# Saturn_Cartage.net
KiCad netlist of a schematic drawn in Altium Designer
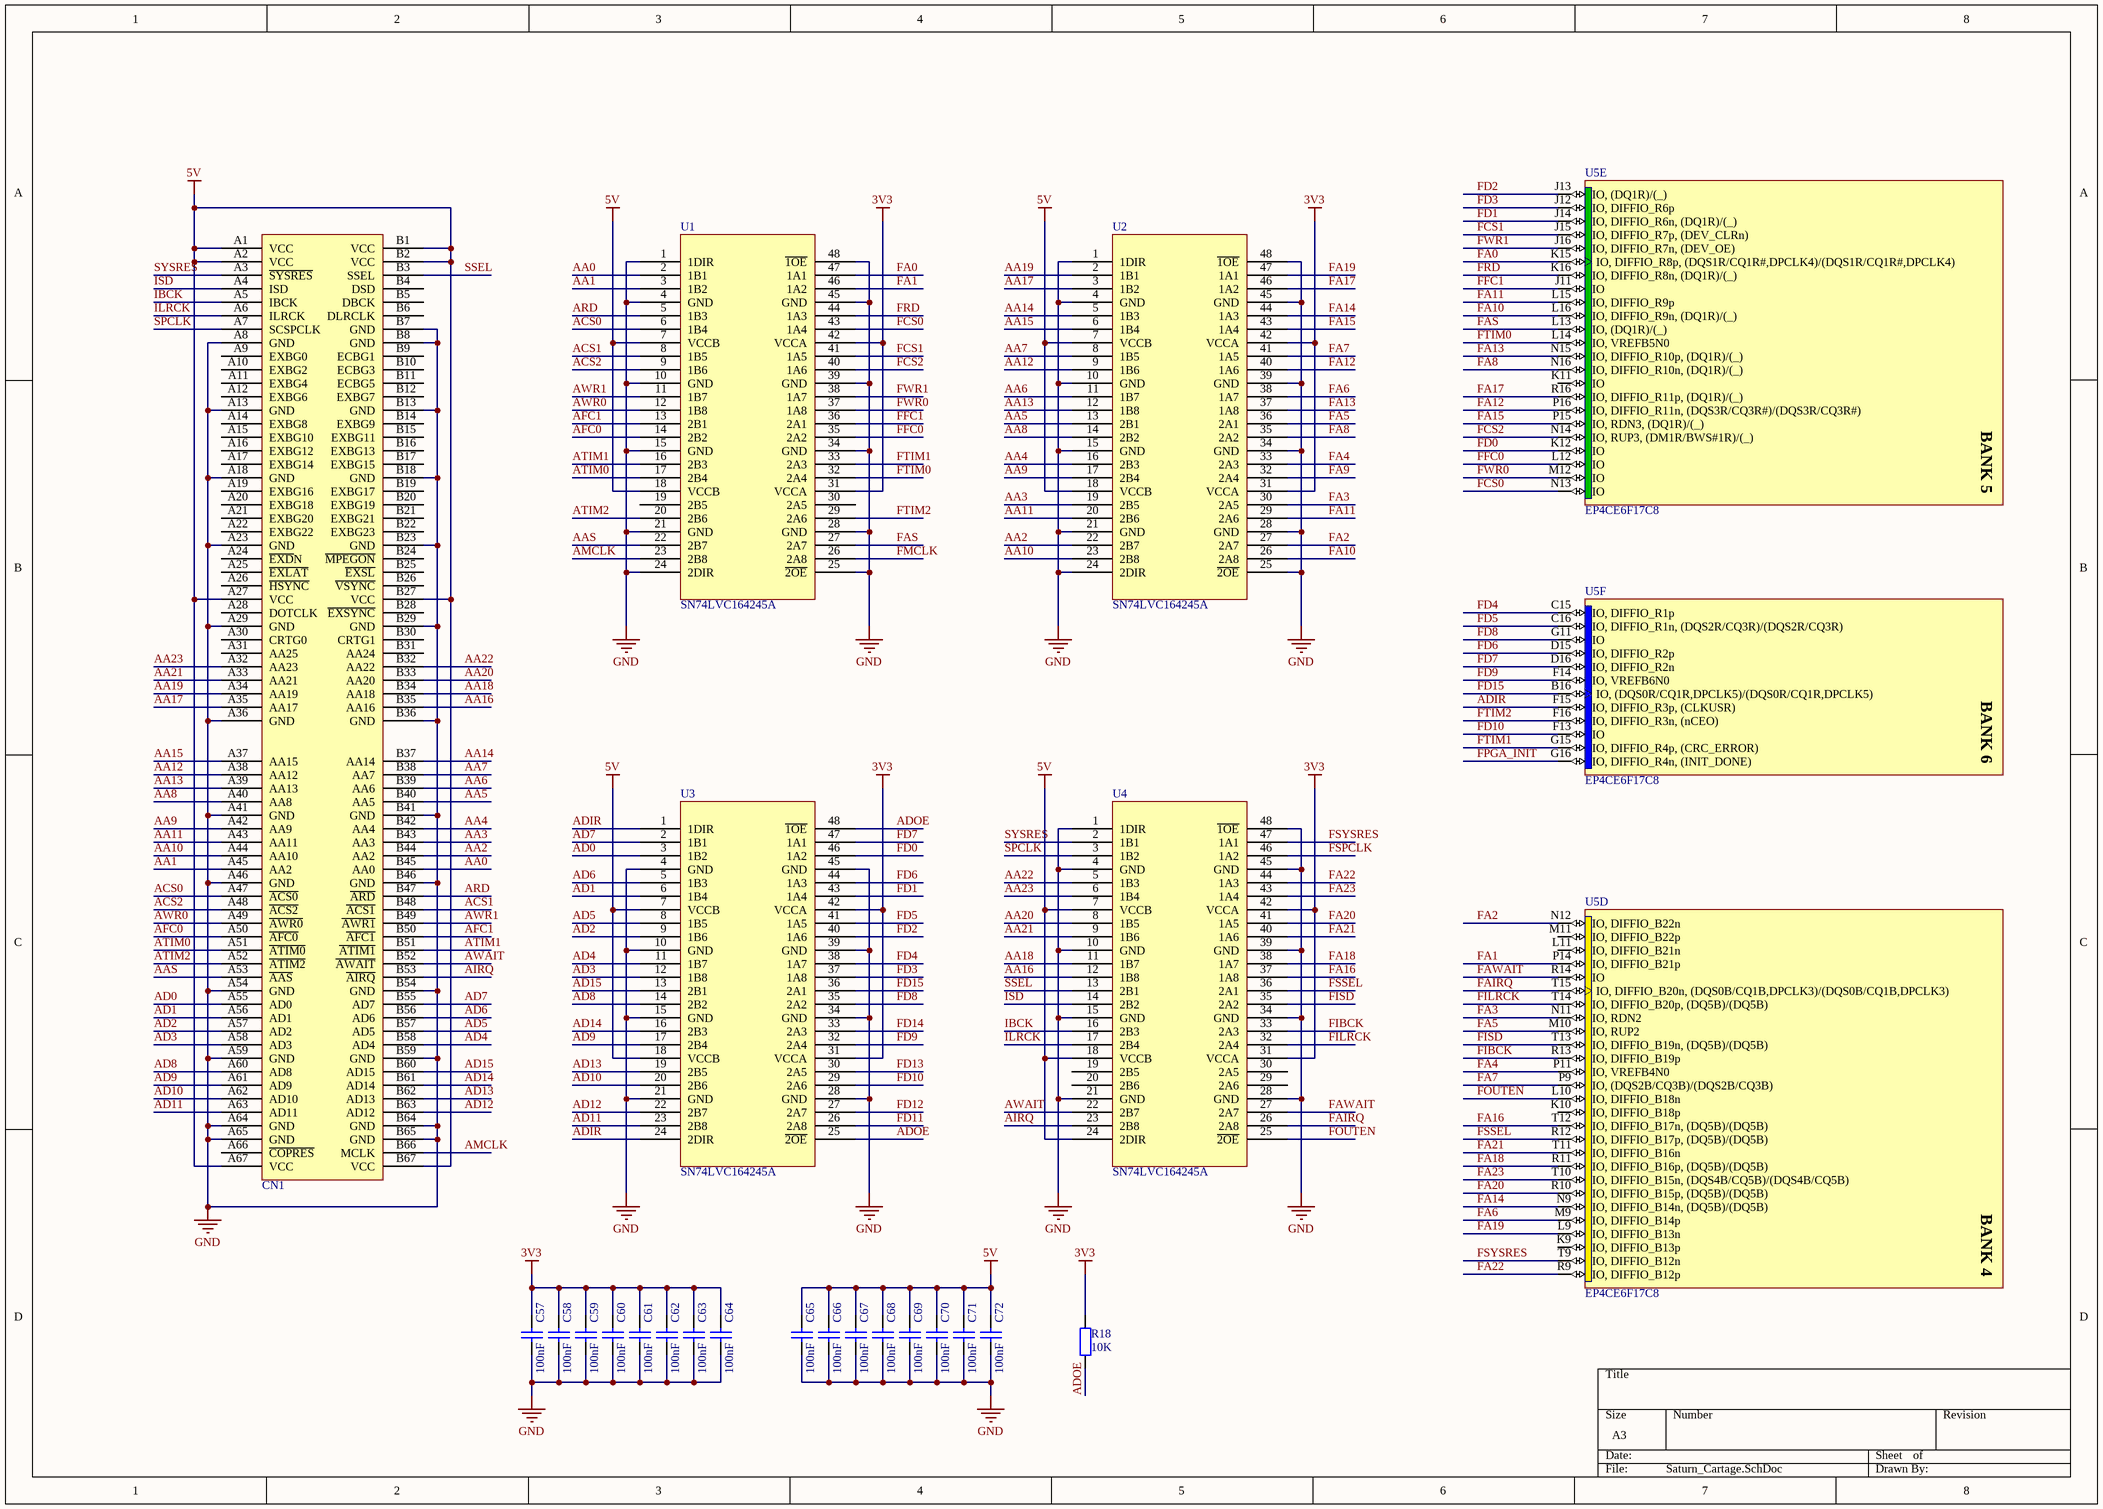
[diagram p0: Saturn_Cartage.SchDoc]

(export (version "E")
  (design (tool "Eeschema 10.0.6"))
  (components
    (comp (ref "C57")
      (value "100nF")
      (footprint "C0603")
      (description "Capacitor")
      (fields (field (name "PUBLISHER") "Altium Limited"))
      (libsource (lib "Miscellaneous Devices") (part "Cap"))
    )
    (comp (ref "C58")
      (value "100nF")
      (footprint "C0603")
      (description "Capacitor")
      (fields (field (name "PUBLISHER") "Altium Limited"))
      (libsource (lib "Miscellaneous Devices") (part "Cap"))
    )
    (comp (ref "C59")
      (value "100nF")
      (footprint "C0603")
      (description "Capacitor")
      (fields (field (name "PUBLISHER") "Altium Limited"))
      (libsource (lib "Miscellaneous Devices") (part "Cap"))
    )
    (comp (ref "C60")
      (value "100nF")
      (footprint "C0603")
      (description "Capacitor")
      (fields (field (name "PUBLISHER") "Altium Limited"))
      (libsource (lib "Miscellaneous Devices") (part "Cap"))
    )
    (comp (ref "C61")
      (value "100nF")
      (footprint "C0603")
      (description "Capacitor")
      (fields (field (name "PUBLISHER") "Altium Limited"))
      (libsource (lib "Miscellaneous Devices") (part "Cap"))
    )
    (comp (ref "C62")
      (value "100nF")
      (footprint "C0603")
      (description "Capacitor")
      (fields (field (name "PUBLISHER") "Altium Limited"))
      (libsource (lib "Miscellaneous Devices") (part "Cap"))
    )
    (comp (ref "C63")
      (value "100nF")
      (footprint "C0603")
      (description "Capacitor")
      (fields (field (name "PUBLISHER") "Altium Limited"))
      (libsource (lib "Miscellaneous Devices") (part "Cap"))
    )
    (comp (ref "C64")
      (value "100nF")
      (footprint "C0603")
      (description "Capacitor")
      (fields (field (name "PUBLISHER") "Altium Limited"))
      (libsource (lib "Miscellaneous Devices") (part "Cap"))
    )
    (comp (ref "C65")
      (value "100nF")
      (footprint "C0603")
      (description "Capacitor")
      (fields (field (name "PUBLISHER") "Altium Limited"))
      (libsource (lib "Miscellaneous Devices") (part "Cap"))
    )
    (comp (ref "C66")
      (value "100nF")
      (footprint "C0603")
      (description "Capacitor")
      (fields (field (name "PUBLISHER") "Altium Limited"))
      (libsource (lib "Miscellaneous Devices") (part "Cap"))
    )
    (comp (ref "C67")
      (value "100nF")
      (footprint "C0603")
      (description "Capacitor")
      (fields (field (name "PUBLISHER") "Altium Limited"))
      (libsource (lib "Miscellaneous Devices") (part "Cap"))
    )
    (comp (ref "C68")
      (value "100nF")
      (footprint "C0603")
      (description "Capacitor")
      (fields (field (name "PUBLISHER") "Altium Limited"))
      (libsource (lib "Miscellaneous Devices") (part "Cap"))
    )
    (comp (ref "C69")
      (value "100nF")
      (footprint "C0603")
      (description "Capacitor")
      (fields (field (name "PUBLISHER") "Altium Limited"))
      (libsource (lib "Miscellaneous Devices") (part "Cap"))
    )
    (comp (ref "C70")
      (value "100nF")
      (footprint "C0603")
      (description "Capacitor")
      (fields (field (name "PUBLISHER") "Altium Limited"))
      (libsource (lib "Miscellaneous Devices") (part "Cap"))
    )
    (comp (ref "C71")
      (value "100nF")
      (footprint "C0603")
      (description "Capacitor")
      (fields (field (name "PUBLISHER") "Altium Limited"))
      (libsource (lib "Miscellaneous Devices") (part "Cap"))
    )
    (comp (ref "C72")
      (value "100nF")
      (footprint "C0603")
      (description "Capacitor")
      (fields (field (name "PUBLISHER") "Altium Limited"))
      (libsource (lib "Miscellaneous Devices") (part "Cap"))
    )
    (comp (ref "CN1")
      (value "SaturnCartage")
      (footprint "Saturn_cart")
      (libsource (lib "ssmaster_1") (part "SaturnCartage"))
    )
    (comp (ref "R18")
      (value "10K")
      (footprint "R0603")
      (description "Resistor")
      (fields (field (name "PUBLISHER") "Altium Limited"))
      (libsource (lib "Miscellaneous Devices") (part "Res2"))
    )
    (comp (ref "U1")
      (value "SN74LVC164245A")
      (footprint "DGG048")
      (libsource (lib "ssmaster_1") (part "SN74LVC164245A"))
    )
    (comp (ref "U2")
      (value "SN74LVC164245A")
      (footprint "DGG048")
      (libsource (lib "ssmaster_1") (part "SN74LVC164245A"))
    )
    (comp (ref "U3")
      (value "SN74LVC164245A")
      (footprint "DGG048")
      (libsource (lib "ssmaster_1") (part "SN74LVC164245A"))
    )
    (comp (ref "U4")
      (value "SN74LVC164245A")
      (footprint "DGG048")
      (libsource (lib "ssmaster_1") (part "SN74LVC164245A"))
    )
    (comp (ref "U5")
      (value "EP4CE6F17C8")
      (footprint "FBGA256")
      (fields (field (name "PUBLISHER") "Altium Limited"))
      (libsource (lib "Altera Cyclone IV E") (part "EP4CE6F17C8"))
    )
  )
  (nets
    (net (code "1") (name "/AA0") (class "Default")
      (node (ref "CN1") (pin "B45") (pinfunction "AA0_B45") (pintype "passive"))
      (node (ref "U1") (pin "2") (pinfunction "1B1_2") (pintype "passive"))
    )
    (net (code "2") (name "/AA1") (class "Default")
      (node (ref "CN1") (pin "A45") (pinfunction "AA2_A45") (pintype "passive"))
      (node (ref "U1") (pin "3") (pinfunction "1B2_3") (pintype "passive"))
    )
    (net (code "3") (name "/AA2") (class "Default")
      (node (ref "CN1") (pin "B44") (pinfunction "AA2_B44") (pintype "passive"))
      (node (ref "U2") (pin "22") (pinfunction "2B7_22") (pintype "passive"))
    )
    (net (code "4") (name "/AA3") (class "Default")
      (node (ref "CN1") (pin "B43") (pinfunction "AA3_B43") (pintype "passive"))
      (node (ref "U2") (pin "19") (pinfunction "2B5_19") (pintype "passive"))
    )
    (net (code "5") (name "/AA4") (class "Default")
      (node (ref "CN1") (pin "B42") (pinfunction "AA4_B42") (pintype "passive"))
      (node (ref "U2") (pin "16") (pinfunction "2B3_16") (pintype "passive"))
    )
    (net (code "6") (name "/AA5") (class "Default")
      (node (ref "CN1") (pin "B40") (pinfunction "AA5_B40") (pintype "passive"))
      (node (ref "U2") (pin "13") (pinfunction "2B1_13") (pintype "passive"))
    )
    (net (code "7") (name "/AA6") (class "Default")
      (node (ref "CN1") (pin "B39") (pinfunction "AA6_B39") (pintype "passive"))
      (node (ref "U2") (pin "11") (pinfunction "1B7_11") (pintype "passive"))
    )
    (net (code "8") (name "/AA7") (class "Default")
      (node (ref "CN1") (pin "B38") (pinfunction "AA7_B38") (pintype "passive"))
      (node (ref "U2") (pin "8") (pinfunction "1B5_8") (pintype "passive"))
    )
    (net (code "9") (name "/AA8") (class "Default")
      (node (ref "CN1") (pin "A40") (pinfunction "AA8_A40") (pintype "passive"))
      (node (ref "U2") (pin "14") (pinfunction "2B2_14") (pintype "passive"))
    )
    (net (code "10") (name "/AA9") (class "Default")
      (node (ref "CN1") (pin "A42") (pinfunction "AA9_A42") (pintype "passive"))
      (node (ref "U2") (pin "17") (pinfunction "2B4_17") (pintype "passive"))
    )
    (net (code "11") (name "/AA10") (class "Default")
      (node (ref "CN1") (pin "A44") (pinfunction "AA10_A44") (pintype "passive"))
      (node (ref "U2") (pin "23") (pinfunction "2B8_23") (pintype "passive"))
    )
    (net (code "12") (name "/AA11") (class "Default")
      (node (ref "CN1") (pin "A43") (pinfunction "AA11_A43") (pintype "passive"))
      (node (ref "U2") (pin "20") (pinfunction "2B6_20") (pintype "passive"))
    )
    (net (code "13") (name "/AA12") (class "Default")
      (node (ref "CN1") (pin "A38") (pinfunction "AA12_A38") (pintype "passive"))
      (node (ref "U2") (pin "9") (pinfunction "1B6_9") (pintype "passive"))
    )
    (net (code "14") (name "/AA13") (class "Default")
      (node (ref "CN1") (pin "A39") (pinfunction "AA13_A39") (pintype "passive"))
      (node (ref "U2") (pin "12") (pinfunction "1B8_12") (pintype "passive"))
    )
    (net (code "15") (name "/AA14") (class "Default")
      (node (ref "CN1") (pin "B37") (pinfunction "AA14_B37") (pintype "passive"))
      (node (ref "U2") (pin "5") (pinfunction "1B3_5") (pintype "passive"))
    )
    (net (code "16") (name "/AA15") (class "Default")
      (node (ref "CN1") (pin "A37") (pinfunction "AA15_A37") (pintype "passive"))
      (node (ref "U2") (pin "6") (pinfunction "1B4_6") (pintype "passive"))
    )
    (net (code "17") (name "/AA16") (class "Default")
      (node (ref "CN1") (pin "B35") (pinfunction "AA16_B35") (pintype "passive"))
      (node (ref "U4") (pin "12") (pinfunction "1B8_12") (pintype "passive"))
    )
    (net (code "18") (name "/AA17") (class "Default")
      (node (ref "CN1") (pin "A35") (pinfunction "AA17_A35") (pintype "passive"))
      (node (ref "U2") (pin "3") (pinfunction "1B2_3") (pintype "passive"))
    )
    (net (code "19") (name "/AA18") (class "Default")
      (node (ref "CN1") (pin "B34") (pinfunction "AA18_B34") (pintype "passive"))
      (node (ref "U4") (pin "11") (pinfunction "1B7_11") (pintype "passive"))
    )
    (net (code "20") (name "/AA19") (class "Default")
      (node (ref "CN1") (pin "A34") (pinfunction "AA19_A34") (pintype "passive"))
      (node (ref "U2") (pin "2") (pinfunction "1B1_2") (pintype "passive"))
    )
    (net (code "21") (name "/AA20") (class "Default")
      (node (ref "CN1") (pin "B33") (pinfunction "AA20_B33") (pintype "passive"))
      (node (ref "U4") (pin "8") (pinfunction "1B5_8") (pintype "passive"))
    )
    (net (code "22") (name "/AA21") (class "Default")
      (node (ref "CN1") (pin "A33") (pinfunction "AA21_A33") (pintype "passive"))
      (node (ref "U4") (pin "9") (pinfunction "1B6_9") (pintype "passive"))
    )
    (net (code "23") (name "/AA22") (class "Default")
      (node (ref "CN1") (pin "B32") (pinfunction "AA22_B32") (pintype "passive"))
      (node (ref "U4") (pin "5") (pinfunction "1B3_5") (pintype "passive"))
    )
    (net (code "24") (name "/AA23") (class "Default")
      (node (ref "CN1") (pin "A32") (pinfunction "AA23_A32") (pintype "passive"))
      (node (ref "U4") (pin "6") (pinfunction "1B4_6") (pintype "passive"))
    )
    (net (code "25") (name "/AAS") (class "Default")
      (node (ref "CN1") (pin "A53") (pinfunction "~{AAS}_A53") (pintype "passive"))
      (node (ref "U1") (pin "22") (pinfunction "2B7_22") (pintype "passive"))
    )
    (net (code "26") (name "/ACS0") (class "Default")
      (node (ref "CN1") (pin "A47") (pinfunction "~{ACS0}_A47") (pintype "passive"))
      (node (ref "U1") (pin "6") (pinfunction "1B4_6") (pintype "passive"))
    )
    (net (code "27") (name "/ACS1") (class "Default")
      (node (ref "CN1") (pin "B48") (pinfunction "~{ACS1}_B48") (pintype "passive"))
      (node (ref "U1") (pin "8") (pinfunction "1B5_8") (pintype "passive"))
    )
    (net (code "28") (name "/ACS2") (class "Default")
      (node (ref "CN1") (pin "A48") (pinfunction "~{ACS2}_A48") (pintype "passive"))
      (node (ref "U1") (pin "9") (pinfunction "1B6_9") (pintype "passive"))
    )
    (net (code "29") (name "/AD0") (class "Default")
      (node (ref "CN1") (pin "A55") (pinfunction "AD0_A55") (pintype "passive"))
      (node (ref "U3") (pin "3") (pinfunction "1B2_3") (pintype "passive"))
    )
    (net (code "30") (name "/AD1") (class "Default")
      (node (ref "CN1") (pin "A56") (pinfunction "AD1_A56") (pintype "passive"))
      (node (ref "U3") (pin "6") (pinfunction "1B4_6") (pintype "passive"))
    )
    (net (code "31") (name "/AD2") (class "Default")
      (node (ref "CN1") (pin "A57") (pinfunction "AD2_A57") (pintype "passive"))
      (node (ref "U3") (pin "9") (pinfunction "1B6_9") (pintype "passive"))
    )
    (net (code "32") (name "/AD3") (class "Default")
      (node (ref "CN1") (pin "A58") (pinfunction "AD3_A58") (pintype "passive"))
      (node (ref "U3") (pin "12") (pinfunction "1B8_12") (pintype "passive"))
    )
    (net (code "33") (name "/AD4") (class "Default")
      (node (ref "CN1") (pin "B58") (pinfunction "AD4_B58") (pintype "passive"))
      (node (ref "U3") (pin "11") (pinfunction "1B7_11") (pintype "passive"))
    )
    (net (code "34") (name "/AD5") (class "Default")
      (node (ref "CN1") (pin "B57") (pinfunction "AD5_B57") (pintype "passive"))
      (node (ref "U3") (pin "8") (pinfunction "1B5_8") (pintype "passive"))
    )
    (net (code "35") (name "/AD6") (class "Default")
      (node (ref "CN1") (pin "B56") (pinfunction "AD6_B56") (pintype "passive"))
      (node (ref "U3") (pin "5") (pinfunction "1B3_5") (pintype "passive"))
    )
    (net (code "36") (name "/AD7") (class "Default")
      (node (ref "CN1") (pin "B55") (pinfunction "AD7_B55") (pintype "passive"))
      (node (ref "U3") (pin "2") (pinfunction "1B1_2") (pintype "passive"))
    )
    (net (code "37") (name "/AD8") (class "Default")
      (node (ref "CN1") (pin "A60") (pinfunction "AD8_A60") (pintype "passive"))
      (node (ref "U3") (pin "14") (pinfunction "2B2_14") (pintype "passive"))
    )
    (net (code "38") (name "/AD9") (class "Default")
      (node (ref "CN1") (pin "A61") (pinfunction "AD9_A61") (pintype "passive"))
      (node (ref "U3") (pin "17") (pinfunction "2B4_17") (pintype "passive"))
    )
    (net (code "39") (name "/AD10") (class "Default")
      (node (ref "CN1") (pin "A62") (pinfunction "AD10_A62") (pintype "passive"))
      (node (ref "U3") (pin "20") (pinfunction "2B6_20") (pintype "passive"))
    )
    (net (code "40") (name "/AD11") (class "Default")
      (node (ref "CN1") (pin "A63") (pinfunction "AD11_A63") (pintype "passive"))
      (node (ref "U3") (pin "23") (pinfunction "2B8_23") (pintype "passive"))
    )
    (net (code "41") (name "/AD12") (class "Default")
      (node (ref "CN1") (pin "B63") (pinfunction "AD12_B63") (pintype "passive"))
      (node (ref "U3") (pin "22") (pinfunction "2B7_22") (pintype "passive"))
    )
    (net (code "42") (name "/AD13") (class "Default")
      (node (ref "CN1") (pin "B62") (pinfunction "AD13_B62") (pintype "passive"))
      (node (ref "U3") (pin "19") (pinfunction "2B5_19") (pintype "passive"))
    )
    (net (code "43") (name "/AD14") (class "Default")
      (node (ref "CN1") (pin "B61") (pinfunction "AD14_B61") (pintype "passive"))
      (node (ref "U3") (pin "16") (pinfunction "2B3_16") (pintype "passive"))
    )
    (net (code "44") (name "/AD15") (class "Default")
      (node (ref "CN1") (pin "B60") (pinfunction "AD15_B60") (pintype "passive"))
      (node (ref "U3") (pin "13") (pinfunction "2B1_13") (pintype "passive"))
    )
    (net (code "45") (name "/ADIR") (class "Default")
      (node (ref "U3") (pin "1") (pinfunction "1DIR_1") (pintype "passive"))
      (node (ref "U3") (pin "24") (pinfunction "2DIR_24") (pintype "passive"))
      (node (ref "U5") (pin "F15") (pinfunction "IO,_DIFFIO_R3p,_(CLKUSR)_F15") (pintype "bidirectional"))
    )
    (net (code "46") (name "/ADOE") (class "Default")
      (node (ref "R18") (pin "1") (pinfunction "1_1") (pintype "passive"))
      (node (ref "U3") (pin "25") (pinfunction "~{2OE}_25") (pintype "passive"))
      (node (ref "U3") (pin "48") (pinfunction "~{1OE}_48") (pintype "passive"))
    )
    (net (code "47") (name "/AFC0") (class "Default")
      (node (ref "CN1") (pin "A50") (pinfunction "~{AFC0}_A50") (pintype "passive"))
      (node (ref "U1") (pin "14") (pinfunction "2B2_14") (pintype "passive"))
    )
    (net (code "48") (name "/AFC1") (class "Default")
      (node (ref "CN1") (pin "B50") (pinfunction "~{AFC1}_B50") (pintype "passive"))
      (node (ref "U1") (pin "13") (pinfunction "2B1_13") (pintype "passive"))
    )
    (net (code "49") (name "/AIRQ") (class "Default")
      (node (ref "CN1") (pin "B53") (pinfunction "~{AIRQ}_B53") (pintype "passive"))
      (node (ref "U4") (pin "23") (pinfunction "2B8_23") (pintype "passive"))
    )
    (net (code "50") (name "/AMCLK") (class "Default")
      (node (ref "CN1") (pin "B66") (pinfunction "MCLK_B66") (pintype "passive"))
      (node (ref "U1") (pin "23") (pinfunction "2B8_23") (pintype "passive"))
    )
    (net (code "51") (name "/ARD") (class "Default")
      (node (ref "CN1") (pin "B47") (pinfunction "~{ARD}_B47") (pintype "passive"))
      (node (ref "U1") (pin "5") (pinfunction "1B3_5") (pintype "passive"))
    )
    (net (code "52") (name "/ATIM0") (class "Default")
      (node (ref "CN1") (pin "A51") (pinfunction "~{ATIM0}_A51") (pintype "passive"))
      (node (ref "U1") (pin "17") (pinfunction "2B4_17") (pintype "passive"))
    )
    (net (code "53") (name "/ATIM1") (class "Default")
      (node (ref "CN1") (pin "B51") (pinfunction "~{ATIM1}_B51") (pintype "passive"))
      (node (ref "U1") (pin "16") (pinfunction "2B3_16") (pintype "passive"))
    )
    (net (code "54") (name "/ATIM2") (class "Default")
      (node (ref "CN1") (pin "A52") (pinfunction "~{ATIM2}_A52") (pintype "passive"))
      (node (ref "U1") (pin "20") (pinfunction "2B6_20") (pintype "passive"))
    )
    (net (code "55") (name "/AWAIT") (class "Default")
      (node (ref "CN1") (pin "B52") (pinfunction "~{AWAIT}_B52") (pintype "passive"))
      (node (ref "U4") (pin "22") (pinfunction "2B7_22") (pintype "passive"))
    )
    (net (code "56") (name "/AWR0") (class "Default")
      (node (ref "CN1") (pin "A49") (pinfunction "~{AWR0}_A49") (pintype "passive"))
      (node (ref "U1") (pin "12") (pinfunction "1B8_12") (pintype "passive"))
    )
    (net (code "57") (name "/AWR1") (class "Default")
      (node (ref "CN1") (pin "B49") (pinfunction "~{AWR1}_B49") (pintype "passive"))
      (node (ref "U1") (pin "11") (pinfunction "1B7_11") (pintype "passive"))
    )
    (net (code "58") (name "/FA0") (class "Default")
      (node (ref "U1") (pin "47") (pinfunction "1A1_47") (pintype "passive"))
      (node (ref "U5") (pin "K15") (pinfunction "IO,_DIFFIO_R8p,_(DQS1R/CQ1R#,DPCLK4)/(DQS1R/CQ1R#,DPCLK4)_K15") (pintype "bidirectional"))
    )
    (net (code "59") (name "/FA1") (class "Default")
      (node (ref "U1") (pin "46") (pinfunction "1A2_46") (pintype "power_in"))
      (node (ref "U5") (pin "P14") (pinfunction "IO,_DIFFIO_B21p_P14") (pintype "bidirectional"))
    )
    (net (code "60") (name "/FA2") (class "Default")
      (node (ref "U2") (pin "27") (pinfunction "2A7_27") (pintype "passive"))
      (node (ref "U5") (pin "N12") (pinfunction "IO,_DIFFIO_B22n_N12") (pintype "bidirectional"))
    )
    (net (code "61") (name "/FA3") (class "Default")
      (node (ref "U2") (pin "30") (pinfunction "2A5_30") (pintype "passive"))
      (node (ref "U5") (pin "N11") (pinfunction "IO,_RDN2_N11") (pintype "bidirectional"))
    )
    (net (code "62") (name "/FA4") (class "Default")
      (node (ref "U2") (pin "33") (pinfunction "2A3_33") (pintype "passive"))
      (node (ref "U5") (pin "P11") (pinfunction "IO,_VREFB4N0_P11") (pintype "bidirectional"))
    )
    (net (code "63") (name "/FA5") (class "Default")
      (node (ref "U2") (pin "36") (pinfunction "2A1_36") (pintype "passive"))
      (node (ref "U5") (pin "M10") (pinfunction "IO,_RUP2_M10") (pintype "bidirectional"))
    )
    (net (code "64") (name "/FA6") (class "Default")
      (node (ref "U2") (pin "38") (pinfunction "1A7_38") (pintype "passive"))
      (node (ref "U5") (pin "M9") (pinfunction "IO,_DIFFIO_B14p_M9") (pintype "bidirectional"))
    )
    (net (code "65") (name "/FA7") (class "Default")
      (node (ref "U2") (pin "41") (pinfunction "1A5_41") (pintype "passive"))
      (node (ref "U5") (pin "P9") (pinfunction "IO,_(DQS2B/CQ3B)/(DQS2B/CQ3B)_P9") (pintype "bidirectional"))
    )
    (net (code "66") (name "/FA8") (class "Default")
      (node (ref "U2") (pin "35") (pinfunction "2A2_35") (pintype "passive"))
      (node (ref "U5") (pin "N16") (pinfunction "IO,_DIFFIO_R10n,_(DQ1R)/(_)_N16") (pintype "bidirectional"))
    )
    (net (code "67") (name "/FA9") (class "Default")
      (node (ref "U2") (pin "32") (pinfunction "2A4_32") (pintype "passive"))
    )
    (net (code "68") (name "/FA10") (class "Default")
      (node (ref "U2") (pin "26") (pinfunction "2A8_26") (pintype "passive"))
      (node (ref "U5") (pin "L16") (pinfunction "IO,_DIFFIO_R9n,_(DQ1R)/(_)_L16") (pintype "bidirectional"))
    )
    (net (code "69") (name "/FA11") (class "Default")
      (node (ref "U2") (pin "29") (pinfunction "2A6_29") (pintype "passive"))
      (node (ref "U5") (pin "L15") (pinfunction "IO,_DIFFIO_R9p_L15") (pintype "bidirectional"))
    )
    (net (code "70") (name "/FA12") (class "Default")
      (node (ref "U2") (pin "40") (pinfunction "1A6_40") (pintype "passive"))
      (node (ref "U5") (pin "P16") (pinfunction "IO,_DIFFIO_R11n,_(DQS3R/CQ3R#)/(DQS3R/CQ3R#)_P16") (pintype "bidirectional"))
    )
    (net (code "71") (name "/FA13") (class "Default")
      (node (ref "U2") (pin "37") (pinfunction "1A8_37") (pintype "passive"))
      (node (ref "U5") (pin "N15") (pinfunction "IO,_DIFFIO_R10p,_(DQ1R)/(_)_N15") (pintype "bidirectional"))
    )
    (net (code "72") (name "/FA14") (class "Default")
      (node (ref "U2") (pin "44") (pinfunction "1A3_44") (pintype "passive"))
      (node (ref "U5") (pin "N9") (pinfunction "IO,_DIFFIO_B14n,_(DQ5B)/(DQ5B)_N9") (pintype "bidirectional"))
    )
    (net (code "73") (name "/FA15") (class "Default")
      (node (ref "U2") (pin "43") (pinfunction "1A4_43") (pintype "passive"))
      (node (ref "U5") (pin "P15") (pinfunction "IO,_RDN3,_(DQ1R)/(_)_P15") (pintype "bidirectional"))
    )
    (net (code "74") (name "/FA16") (class "Default")
      (node (ref "U4") (pin "37") (pinfunction "1A8_37") (pintype "passive"))
      (node (ref "U5") (pin "T12") (pinfunction "IO,_DIFFIO_B17n,_(DQ5B)/(DQ5B)_T12") (pintype "bidirectional"))
    )
    (net (code "75") (name "/FA17") (class "Default")
      (node (ref "U2") (pin "46") (pinfunction "1A2_46") (pintype "power_in"))
      (node (ref "U5") (pin "R16") (pinfunction "IO,_DIFFIO_R11p,_(DQ1R)/(_)_R16") (pintype "bidirectional"))
    )
    (net (code "76") (name "/FA18") (class "Default")
      (node (ref "U4") (pin "38") (pinfunction "1A7_38") (pintype "passive"))
      (node (ref "U5") (pin "R11") (pinfunction "IO,_DIFFIO_B16p,_(DQ5B)/(DQ5B)_R11") (pintype "bidirectional"))
    )
    (net (code "77") (name "/FA19") (class "Default")
      (node (ref "U2") (pin "47") (pinfunction "1A1_47") (pintype "passive"))
      (node (ref "U5") (pin "L9") (pinfunction "IO,_DIFFIO_B13n_L9") (pintype "bidirectional"))
    )
    (net (code "78") (name "/FA20") (class "Default")
      (node (ref "U4") (pin "41") (pinfunction "1A5_41") (pintype "passive"))
      (node (ref "U5") (pin "R10") (pinfunction "IO,_DIFFIO_B15p,_(DQ5B)/(DQ5B)_R10") (pintype "bidirectional"))
    )
    (net (code "79") (name "/FA21") (class "Default")
      (node (ref "U4") (pin "40") (pinfunction "1A6_40") (pintype "passive"))
      (node (ref "U5") (pin "T11") (pinfunction "IO,_DIFFIO_B16n_T11") (pintype "bidirectional"))
    )
    (net (code "80") (name "/FA22") (class "Default")
      (node (ref "U4") (pin "44") (pinfunction "1A3_44") (pintype "passive"))
      (node (ref "U5") (pin "R9") (pinfunction "IO,_DIFFIO_B12p_R9") (pintype "bidirectional"))
    )
    (net (code "81") (name "/FA23") (class "Default")
      (node (ref "U4") (pin "43") (pinfunction "1A4_43") (pintype "passive"))
      (node (ref "U5") (pin "T10") (pinfunction "IO,_DIFFIO_B15n,_(DQS4B/CQ5B)/(DQS4B/CQ5B)_T10") (pintype "bidirectional"))
    )
    (net (code "82") (name "/FAIRQ") (class "Default")
      (node (ref "U4") (pin "26") (pinfunction "2A8_26") (pintype "passive"))
      (node (ref "U5") (pin "T15") (pinfunction "IO,_DIFFIO_B20n,_(DQS0B/CQ1B,DPCLK3)/(DQS0B/CQ1B,DPCLK3)_T15") (pintype "bidirectional"))
    )
    (net (code "83") (name "/FAS") (class "Default")
      (node (ref "U1") (pin "27") (pinfunction "2A7_27") (pintype "passive"))
      (node (ref "U5") (pin "L13") (pinfunction "IO,_(DQ1R)/(_)_L13") (pintype "bidirectional"))
    )
    (net (code "84") (name "/FAWAIT") (class "Default")
      (node (ref "U4") (pin "27") (pinfunction "2A7_27") (pintype "passive"))
      (node (ref "U5") (pin "R14") (pinfunction "IO_R14") (pintype "bidirectional"))
    )
    (net (code "85") (name "/FCS0") (class "Default")
      (node (ref "U1") (pin "43") (pinfunction "1A4_43") (pintype "passive"))
      (node (ref "U5") (pin "N13") (pinfunction "IO_N13") (pintype "bidirectional"))
    )
    (net (code "86") (name "/FCS1") (class "Default")
      (node (ref "U1") (pin "41") (pinfunction "1A5_41") (pintype "passive"))
      (node (ref "U5") (pin "J15") (pinfunction "IO,_DIFFIO_R7p,_(DEV_CLRn)_J15") (pintype "bidirectional"))
    )
    (net (code "87") (name "/FCS2") (class "Default")
      (node (ref "U1") (pin "40") (pinfunction "1A6_40") (pintype "passive"))
      (node (ref "U5") (pin "N14") (pinfunction "IO,_RUP3,_(DM1R/BWS#1R)/(_)_N14") (pintype "bidirectional"))
    )
    (net (code "88") (name "/FD0") (class "Default")
      (node (ref "U3") (pin "46") (pinfunction "1A2_46") (pintype "power_in"))
      (node (ref "U5") (pin "K12") (pinfunction "IO_K12") (pintype "bidirectional"))
    )
    (net (code "89") (name "/FD1") (class "Default")
      (node (ref "U3") (pin "43") (pinfunction "1A4_43") (pintype "passive"))
      (node (ref "U5") (pin "J14") (pinfunction "IO,_DIFFIO_R6n,_(DQ1R)/(_)_J14") (pintype "bidirectional"))
    )
    (net (code "90") (name "/FD2") (class "Default")
      (node (ref "U3") (pin "40") (pinfunction "1A6_40") (pintype "passive"))
      (node (ref "U5") (pin "J13") (pinfunction "IO,_(DQ1R)/(_)_J13") (pintype "bidirectional"))
    )
    (net (code "91") (name "/FD3") (class "Default")
      (node (ref "U3") (pin "37") (pinfunction "1A8_37") (pintype "passive"))
      (node (ref "U5") (pin "J12") (pinfunction "IO,_DIFFIO_R6p_J12") (pintype "bidirectional"))
    )
    (net (code "92") (name "/FD4") (class "Default")
      (node (ref "U3") (pin "38") (pinfunction "1A7_38") (pintype "passive"))
      (node (ref "U5") (pin "C15") (pinfunction "IO,_DIFFIO_R1p_C15") (pintype "bidirectional"))
    )
    (net (code "93") (name "/FD5") (class "Default")
      (node (ref "U3") (pin "41") (pinfunction "1A5_41") (pintype "passive"))
      (node (ref "U5") (pin "C16") (pinfunction "IO,_DIFFIO_R1n,_(DQS2R/CQ3R)/(DQS2R/CQ3R)_C16") (pintype "bidirectional"))
    )
    (net (code "94") (name "/FD6") (class "Default")
      (node (ref "U3") (pin "44") (pinfunction "1A3_44") (pintype "passive"))
      (node (ref "U5") (pin "D15") (pinfunction "IO,_DIFFIO_R2p_D15") (pintype "bidirectional"))
    )
    (net (code "95") (name "/FD7") (class "Default")
      (node (ref "U3") (pin "47") (pinfunction "1A1_47") (pintype "passive"))
      (node (ref "U5") (pin "D16") (pinfunction "IO,_DIFFIO_R2n_D16") (pintype "bidirectional"))
    )
    (net (code "96") (name "/FD8") (class "Default")
      (node (ref "U3") (pin "35") (pinfunction "2A2_35") (pintype "passive"))
      (node (ref "U5") (pin "G11") (pinfunction "IO_G11") (pintype "bidirectional"))
    )
    (net (code "97") (name "/FD9") (class "Default")
      (node (ref "U3") (pin "32") (pinfunction "2A4_32") (pintype "passive"))
      (node (ref "U5") (pin "F14") (pinfunction "IO,_VREFB6N0_F14") (pintype "bidirectional"))
    )
    (net (code "98") (name "/FD10") (class "Default")
      (node (ref "U3") (pin "29") (pinfunction "2A6_29") (pintype "passive"))
      (node (ref "U5") (pin "F13") (pinfunction "IO_F13") (pintype "bidirectional"))
    )
    (net (code "99") (name "/FD11") (class "Default")
      (node (ref "U3") (pin "26") (pinfunction "2A8_26") (pintype "passive"))
    )
    (net (code "100") (name "/FD12") (class "Default")
      (node (ref "U3") (pin "27") (pinfunction "2A7_27") (pintype "passive"))
    )
    (net (code "101") (name "/FD13") (class "Default")
      (node (ref "U3") (pin "30") (pinfunction "2A5_30") (pintype "passive"))
    )
    (net (code "102") (name "/FD14") (class "Default")
      (node (ref "U3") (pin "33") (pinfunction "2A3_33") (pintype "passive"))
    )
    (net (code "103") (name "/FD15") (class "Default")
      (node (ref "U3") (pin "36") (pinfunction "2A1_36") (pintype "passive"))
      (node (ref "U5") (pin "B16") (pinfunction "IO,_(DQS0R/CQ1R,DPCLK5)/(DQS0R/CQ1R,DPCLK5)_B16") (pintype "bidirectional"))
    )
    (net (code "104") (name "/FFC0") (class "Default")
      (node (ref "U1") (pin "35") (pinfunction "2A2_35") (pintype "passive"))
      (node (ref "U5") (pin "L12") (pinfunction "IO_L12") (pintype "bidirectional"))
    )
    (net (code "105") (name "/FFC1") (class "Default")
      (node (ref "U1") (pin "36") (pinfunction "2A1_36") (pintype "passive"))
      (node (ref "U5") (pin "J11") (pinfunction "IO_J11") (pintype "bidirectional"))
    )
    (net (code "106") (name "/FIBCK") (class "Default")
      (node (ref "U4") (pin "33") (pinfunction "2A3_33") (pintype "passive"))
      (node (ref "U5") (pin "R13") (pinfunction "IO,_DIFFIO_B19p_R13") (pintype "bidirectional"))
    )
    (net (code "107") (name "/FILRCK") (class "Default")
      (node (ref "U4") (pin "32") (pinfunction "2A4_32") (pintype "passive"))
      (node (ref "U5") (pin "T14") (pinfunction "IO,_DIFFIO_B20p,_(DQ5B)/(DQ5B)_T14") (pintype "bidirectional"))
    )
    (net (code "108") (name "/FISD") (class "Default")
      (node (ref "U4") (pin "35") (pinfunction "2A2_35") (pintype "passive"))
      (node (ref "U5") (pin "T13") (pinfunction "IO,_DIFFIO_B19n,_(DQ5B)/(DQ5B)_T13") (pintype "bidirectional"))
    )
    (net (code "109") (name "/FMCLK") (class "Default")
      (node (ref "U1") (pin "26") (pinfunction "2A8_26") (pintype "passive"))
    )
    (net (code "110") (name "/FOUTEN") (class "Default")
      (node (ref "U4") (pin "25") (pinfunction "~{2OE}_25") (pintype "passive"))
      (node (ref "U5") (pin "L10") (pinfunction "IO,_DIFFIO_B18n_L10") (pintype "bidirectional"))
    )
    (net (code "111") (name "/FPGA_INIT") (class "Default")
      (node (ref "U5") (pin "G16") (pinfunction "IO,_DIFFIO_R4n,_(INIT_DONE)_G16") (pintype "bidirectional"))
    )
    (net (code "112") (name "/FRD") (class "Default")
      (node (ref "U1") (pin "44") (pinfunction "1A3_44") (pintype "passive"))
      (node (ref "U5") (pin "K16") (pinfunction "IO,_DIFFIO_R8n,_(DQ1R)/(_)_K16") (pintype "bidirectional"))
    )
    (net (code "113") (name "/FSPCLK") (class "Default")
      (node (ref "U4") (pin "46") (pinfunction "1A2_46") (pintype "power_in"))
    )
    (net (code "114") (name "/FSSEL") (class "Default")
      (node (ref "U4") (pin "36") (pinfunction "2A1_36") (pintype "passive"))
      (node (ref "U5") (pin "R12") (pinfunction "IO,_DIFFIO_B17p,_(DQ5B)/(DQ5B)_R12") (pintype "bidirectional"))
    )
    (net (code "115") (name "/FSYSRES") (class "Default")
      (node (ref "U4") (pin "47") (pinfunction "1A1_47") (pintype "passive"))
      (node (ref "U5") (pin "T9") (pinfunction "IO,_DIFFIO_B12n_T9") (pintype "bidirectional"))
    )
    (net (code "116") (name "/FTIM0") (class "Default")
      (node (ref "U1") (pin "32") (pinfunction "2A4_32") (pintype "passive"))
      (node (ref "U5") (pin "L14") (pinfunction "IO,_VREFB5N0_L14") (pintype "bidirectional"))
    )
    (net (code "117") (name "/FTIM1") (class "Default")
      (node (ref "U1") (pin "33") (pinfunction "2A3_33") (pintype "passive"))
      (node (ref "U5") (pin "G15") (pinfunction "IO,_DIFFIO_R4p,_(CRC_ERROR)_G15") (pintype "bidirectional"))
    )
    (net (code "118") (name "/FTIM2") (class "Default")
      (node (ref "U1") (pin "29") (pinfunction "2A6_29") (pintype "passive"))
      (node (ref "U5") (pin "F16") (pinfunction "IO,_DIFFIO_R3n,_(nCEO)_F16") (pintype "bidirectional"))
    )
    (net (code "119") (name "/FWR0") (class "Default")
      (node (ref "U1") (pin "37") (pinfunction "1A8_37") (pintype "passive"))
      (node (ref "U5") (pin "M12") (pinfunction "IO_M12") (pintype "bidirectional"))
    )
    (net (code "120") (name "/FWR1") (class "Default")
      (node (ref "U1") (pin "38") (pinfunction "1A7_38") (pintype "passive"))
      (node (ref "U5") (pin "J16") (pinfunction "IO,_DIFFIO_R7n,_(DEV_OE)_J16") (pintype "bidirectional"))
    )
    (net (code "121") (name "/IBCK") (class "Default")
      (node (ref "CN1") (pin "A5") (pinfunction "IBCK_A5") (pintype "passive"))
      (node (ref "U4") (pin "16") (pinfunction "2B3_16") (pintype "passive"))
    )
    (net (code "122") (name "/ILRCK") (class "Default")
      (node (ref "CN1") (pin "A6") (pinfunction "ILRCK_A6") (pintype "passive"))
      (node (ref "U4") (pin "17") (pinfunction "2B4_17") (pintype "passive"))
    )
    (net (code "123") (name "/ISD") (class "Default")
      (node (ref "CN1") (pin "A4") (pinfunction "ISD_A4") (pintype "passive"))
      (node (ref "U4") (pin "14") (pinfunction "2B2_14") (pintype "passive"))
    )
    (net (code "124") (name "/SPCLK") (class "Default")
      (node (ref "CN1") (pin "A7") (pinfunction "SCSPCLK_A7") (pintype "passive"))
      (node (ref "U4") (pin "3") (pinfunction "1B2_3") (pintype "passive"))
    )
    (net (code "125") (name "/SSEL") (class "Default")
      (node (ref "CN1") (pin "B3") (pinfunction "SSEL_B3") (pintype "passive"))
      (node (ref "U4") (pin "13") (pinfunction "2B1_13") (pintype "passive"))
    )
    (net (code "126") (name "/SYSRES") (class "Default")
      (node (ref "CN1") (pin "A3") (pinfunction "~{SYSRES}_A3") (pintype "passive"))
      (node (ref "U4") (pin "2") (pinfunction "1B1_2") (pintype "passive"))
    )
    (net (code "127") (name "3V3") (class "Default")
      (node (ref "C57") (pin "2") (pinfunction "2_2") (pintype "passive"))
      (node (ref "C58") (pin "2") (pinfunction "2_2") (pintype "passive"))
      (node (ref "C59") (pin "2") (pinfunction "2_2") (pintype "passive"))
      (node (ref "C60") (pin "2") (pinfunction "2_2") (pintype "passive"))
      (node (ref "C61") (pin "2") (pinfunction "2_2") (pintype "passive"))
      (node (ref "C62") (pin "2") (pinfunction "2_2") (pintype "passive"))
      (node (ref "C63") (pin "2") (pinfunction "2_2") (pintype "passive"))
      (node (ref "C64") (pin "2") (pinfunction "2_2") (pintype "passive"))
      (node (ref "R18") (pin "2") (pinfunction "2_2") (pintype "passive"))
      (node (ref "U1") (pin "31") (pinfunction "VCCA_31") (pintype "power_in"))
      (node (ref "U1") (pin "42") (pinfunction "VCCA_42") (pintype "power_in"))
      (node (ref "U2") (pin "31") (pinfunction "VCCA_31") (pintype "power_in"))
      (node (ref "U2") (pin "42") (pinfunction "VCCA_42") (pintype "power_in"))
      (node (ref "U3") (pin "31") (pinfunction "VCCA_31") (pintype "power_in"))
      (node (ref "U3") (pin "42") (pinfunction "VCCA_42") (pintype "power_in"))
      (node (ref "U4") (pin "31") (pinfunction "VCCA_31") (pintype "power_in"))
      (node (ref "U4") (pin "42") (pinfunction "VCCA_42") (pintype "power_in"))
    )
    (net (code "128") (name "5V") (class "Default")
      (node (ref "C65") (pin "2") (pinfunction "2_2") (pintype "passive"))
      (node (ref "C66") (pin "2") (pinfunction "2_2") (pintype "passive"))
      (node (ref "C67") (pin "2") (pinfunction "2_2") (pintype "passive"))
      (node (ref "C68") (pin "2") (pinfunction "2_2") (pintype "passive"))
      (node (ref "C69") (pin "2") (pinfunction "2_2") (pintype "passive"))
      (node (ref "C70") (pin "2") (pinfunction "2_2") (pintype "passive"))
      (node (ref "C71") (pin "2") (pinfunction "2_2") (pintype "passive"))
      (node (ref "C72") (pin "2") (pinfunction "2_2") (pintype "passive"))
      (node (ref "CN1") (pin "A1") (pinfunction "VCC_A1") (pintype "passive"))
      (node (ref "CN1") (pin "A2") (pinfunction "VCC_A2") (pintype "passive"))
      (node (ref "CN1") (pin "A27") (pinfunction "VCC_A27") (pintype "passive"))
      (node (ref "CN1") (pin "A67") (pinfunction "VCC_A67") (pintype "passive"))
      (node (ref "CN1") (pin "B1") (pinfunction "VCC_B1") (pintype "passive"))
      (node (ref "CN1") (pin "B2") (pinfunction "VCC_B2") (pintype "passive"))
      (node (ref "CN1") (pin "B27") (pinfunction "VCC_B27") (pintype "passive"))
      (node (ref "CN1") (pin "B67") (pinfunction "VCC_B67") (pintype "passive"))
      (node (ref "U1") (pin "18") (pinfunction "VCCB_18") (pintype "power_in"))
      (node (ref "U1") (pin "7") (pinfunction "VCCB_7") (pintype "power_in"))
      (node (ref "U2") (pin "18") (pinfunction "VCCB_18") (pintype "power_in"))
      (node (ref "U2") (pin "7") (pinfunction "VCCB_7") (pintype "power_in"))
      (node (ref "U3") (pin "18") (pinfunction "VCCB_18") (pintype "power_in"))
      (node (ref "U3") (pin "7") (pinfunction "VCCB_7") (pintype "power_in"))
      (node (ref "U4") (pin "18") (pinfunction "VCCB_18") (pintype "power_in"))
      (node (ref "U4") (pin "24") (pinfunction "2DIR_24") (pintype "passive"))
      (node (ref "U4") (pin "7") (pinfunction "VCCB_7") (pintype "power_in"))
    )
    (net (code "129") (name "GND") (class "Default")
      (node (ref "C57") (pin "1") (pinfunction "1_1") (pintype "passive"))
      (node (ref "C58") (pin "1") (pinfunction "1_1") (pintype "passive"))
      (node (ref "C59") (pin "1") (pinfunction "1_1") (pintype "passive"))
      (node (ref "C60") (pin "1") (pinfunction "1_1") (pintype "passive"))
      (node (ref "C61") (pin "1") (pinfunction "1_1") (pintype "passive"))
      (node (ref "C62") (pin "1") (pinfunction "1_1") (pintype "passive"))
      (node (ref "C63") (pin "1") (pinfunction "1_1") (pintype "passive"))
      (node (ref "C64") (pin "1") (pinfunction "1_1") (pintype "passive"))
      (node (ref "C65") (pin "1") (pinfunction "1_1") (pintype "passive"))
      (node (ref "C66") (pin "1") (pinfunction "1_1") (pintype "passive"))
      (node (ref "C67") (pin "1") (pinfunction "1_1") (pintype "passive"))
      (node (ref "C68") (pin "1") (pinfunction "1_1") (pintype "passive"))
      (node (ref "C69") (pin "1") (pinfunction "1_1") (pintype "passive"))
      (node (ref "C70") (pin "1") (pinfunction "1_1") (pintype "passive"))
      (node (ref "C71") (pin "1") (pinfunction "1_1") (pintype "passive"))
      (node (ref "C72") (pin "1") (pinfunction "1_1") (pintype "passive"))
      (node (ref "CN1") (pin "A13") (pinfunction "GND_A13") (pintype "passive"))
      (node (ref "CN1") (pin "A18") (pinfunction "GND_A18") (pintype "passive"))
      (node (ref "CN1") (pin "A23") (pinfunction "GND_A23") (pintype "passive"))
      (node (ref "CN1") (pin "A29") (pinfunction "GND_A29") (pintype "passive"))
      (node (ref "CN1") (pin "A36") (pinfunction "GND_A36") (pintype "passive"))
      (node (ref "CN1") (pin "A41") (pinfunction "GND_A41") (pintype "passive"))
      (node (ref "CN1") (pin "A46") (pinfunction "GND_A46") (pintype "passive"))
      (node (ref "CN1") (pin "A54") (pinfunction "GND_A54") (pintype "passive"))
      (node (ref "CN1") (pin "A59") (pinfunction "GND_A59") (pintype "passive"))
      (node (ref "CN1") (pin "A64") (pinfunction "GND_A64") (pintype "passive"))
      (node (ref "CN1") (pin "A65") (pinfunction "GND_A65") (pintype "passive"))
      (node (ref "CN1") (pin "A8") (pinfunction "GND_A8") (pintype "passive"))
      (node (ref "CN1") (pin "B13") (pinfunction "GND_B13") (pintype "passive"))
      (node (ref "CN1") (pin "B18") (pinfunction "GND_B18") (pintype "passive"))
      (node (ref "CN1") (pin "B23") (pinfunction "GND_B23") (pintype "passive"))
      (node (ref "CN1") (pin "B29") (pinfunction "GND_B29") (pintype "passive"))
      (node (ref "CN1") (pin "B36") (pinfunction "GND_B36") (pintype "passive"))
      (node (ref "CN1") (pin "B41") (pinfunction "GND_B41") (pintype "passive"))
      (node (ref "CN1") (pin "B46") (pinfunction "GND_B46") (pintype "passive"))
      (node (ref "CN1") (pin "B54") (pinfunction "GND_B54") (pintype "passive"))
      (node (ref "CN1") (pin "B59") (pinfunction "GND_B59") (pintype "passive"))
      (node (ref "CN1") (pin "B64") (pinfunction "GND_B64") (pintype "passive"))
      (node (ref "CN1") (pin "B65") (pinfunction "GND_B65") (pintype "passive"))
      (node (ref "CN1") (pin "B7") (pinfunction "GND_B7") (pintype "passive"))
      (node (ref "CN1") (pin "B8") (pinfunction "GND_B8") (pintype "passive"))
      (node (ref "U1") (pin "1") (pinfunction "1DIR_1") (pintype "passive"))
      (node (ref "U1") (pin "10") (pinfunction "GND_10") (pintype "power_in"))
      (node (ref "U1") (pin "15") (pinfunction "GND_15") (pintype "power_in"))
      (node (ref "U1") (pin "21") (pinfunction "GND_21") (pintype "power_in"))
      (node (ref "U1") (pin "24") (pinfunction "2DIR_24") (pintype "passive"))
      (node (ref "U1") (pin "25") (pinfunction "~{2OE}_25") (pintype "passive"))
      (node (ref "U1") (pin "28") (pinfunction "GND_28") (pintype "power_in"))
      (node (ref "U1") (pin "34") (pinfunction "GND_34") (pintype "power_in"))
      (node (ref "U1") (pin "39") (pinfunction "GND_39") (pintype "power_in"))
      (node (ref "U1") (pin "4") (pinfunction "GND_4") (pintype "power_in"))
      (node (ref "U1") (pin "45") (pinfunction "GND_45") (pintype "power_in"))
      (node (ref "U1") (pin "48") (pinfunction "~{1OE}_48") (pintype "passive"))
      (node (ref "U2") (pin "1") (pinfunction "1DIR_1") (pintype "passive"))
      (node (ref "U2") (pin "10") (pinfunction "GND_10") (pintype "power_in"))
      (node (ref "U2") (pin "15") (pinfunction "GND_15") (pintype "power_in"))
      (node (ref "U2") (pin "21") (pinfunction "GND_21") (pintype "power_in"))
      (node (ref "U2") (pin "24") (pinfunction "2DIR_24") (pintype "passive"))
      (node (ref "U2") (pin "25") (pinfunction "~{2OE}_25") (pintype "passive"))
      (node (ref "U2") (pin "28") (pinfunction "GND_28") (pintype "power_in"))
      (node (ref "U2") (pin "34") (pinfunction "GND_34") (pintype "power_in"))
      (node (ref "U2") (pin "39") (pinfunction "GND_39") (pintype "power_in"))
      (node (ref "U2") (pin "4") (pinfunction "GND_4") (pintype "power_in"))
      (node (ref "U2") (pin "45") (pinfunction "GND_45") (pintype "power_in"))
      (node (ref "U2") (pin "48") (pinfunction "~{1OE}_48") (pintype "passive"))
      (node (ref "U3") (pin "10") (pinfunction "GND_10") (pintype "power_in"))
      (node (ref "U3") (pin "15") (pinfunction "GND_15") (pintype "power_in"))
      (node (ref "U3") (pin "21") (pinfunction "GND_21") (pintype "power_in"))
      (node (ref "U3") (pin "28") (pinfunction "GND_28") (pintype "power_in"))
      (node (ref "U3") (pin "34") (pinfunction "GND_34") (pintype "power_in"))
      (node (ref "U3") (pin "39") (pinfunction "GND_39") (pintype "power_in"))
      (node (ref "U3") (pin "4") (pinfunction "GND_4") (pintype "power_in"))
      (node (ref "U3") (pin "45") (pinfunction "GND_45") (pintype "power_in"))
      (node (ref "U4") (pin "1") (pinfunction "1DIR_1") (pintype "passive"))
      (node (ref "U4") (pin "10") (pinfunction "GND_10") (pintype "power_in"))
      (node (ref "U4") (pin "15") (pinfunction "GND_15") (pintype "power_in"))
      (node (ref "U4") (pin "21") (pinfunction "GND_21") (pintype "power_in"))
      (node (ref "U4") (pin "28") (pinfunction "GND_28") (pintype "power_in"))
      (node (ref "U4") (pin "34") (pinfunction "GND_34") (pintype "power_in"))
      (node (ref "U4") (pin "39") (pinfunction "GND_39") (pintype "power_in"))
      (node (ref "U4") (pin "4") (pinfunction "GND_4") (pintype "power_in"))
      (node (ref "U4") (pin "45") (pinfunction "GND_45") (pintype "power_in"))
      (node (ref "U4") (pin "48") (pinfunction "~{1OE}_48") (pintype "passive"))
    )
    (net (code "130") (name "unconnected-(CN1-AA24-PadB31)") (class "Default")
      (node (ref "CN1") (pin "B31") (pinfunction "AA24_B31") (pintype "passive"))
    )
    (net (code "131") (name "unconnected-(CN1-AA25-PadA31)") (class "Default")
      (node (ref "CN1") (pin "A31") (pinfunction "AA25_A31") (pintype "passive"))
    )
    (net (code "132") (name "unconnected-(CN1-CRTG0-PadA30)") (class "Default")
      (node (ref "CN1") (pin "A30") (pinfunction "CRTG0_A30") (pintype "passive"))
    )
    (net (code "133") (name "unconnected-(CN1-CRTG1-PadB30)") (class "Default")
      (node (ref "CN1") (pin "B30") (pinfunction "CRTG1_B30") (pintype "passive"))
    )
    (net (code "134") (name "unconnected-(CN1-DBCK-PadB5)") (class "Default")
      (node (ref "CN1") (pin "B5") (pinfunction "DBCK_B5") (pintype "passive"))
    )
    (net (code "135") (name "unconnected-(CN1-DLRCLK-PadB6)") (class "Default")
      (node (ref "CN1") (pin "B6") (pinfunction "DLRCLK_B6") (pintype "passive"))
    )
    (net (code "136") (name "unconnected-(CN1-DOTCLK-PadA28)") (class "Default")
      (node (ref "CN1") (pin "A28") (pinfunction "DOTCLK_A28") (pintype "passive"))
    )
    (net (code "137") (name "unconnected-(CN1-DSD-PadB4)") (class "Default")
      (node (ref "CN1") (pin "B4") (pinfunction "DSD_B4") (pintype "passive"))
    )
    (net (code "138") (name "unconnected-(CN1-ECBG1-PadB9)") (class "Default")
      (node (ref "CN1") (pin "B9") (pinfunction "ECBG1_B9") (pintype "passive"))
    )
    (net (code "139") (name "unconnected-(CN1-ECBG3-PadB10)") (class "Default")
      (node (ref "CN1") (pin "B10") (pinfunction "ECBG3_B10") (pintype "passive"))
    )
    (net (code "140") (name "unconnected-(CN1-ECBG5-PadB11)") (class "Default")
      (node (ref "CN1") (pin "B11") (pinfunction "ECBG5_B11") (pintype "passive"))
    )
    (net (code "141") (name "unconnected-(CN1-EXBG0-PadA9)") (class "Default")
      (node (ref "CN1") (pin "A9") (pinfunction "EXBG0_A9") (pintype "passive"))
    )
    (net (code "142") (name "unconnected-(CN1-EXBG2-PadA10)") (class "Default")
      (node (ref "CN1") (pin "A10") (pinfunction "EXBG2_A10") (pintype "passive"))
    )
    (net (code "143") (name "unconnected-(CN1-EXBG4-PadA11)") (class "Default")
      (node (ref "CN1") (pin "A11") (pinfunction "EXBG4_A11") (pintype "passive"))
    )
    (net (code "144") (name "unconnected-(CN1-EXBG6-PadA12)") (class "Default")
      (node (ref "CN1") (pin "A12") (pinfunction "EXBG6_A12") (pintype "passive"))
    )
    (net (code "145") (name "unconnected-(CN1-EXBG7-PadB12)") (class "Default")
      (node (ref "CN1") (pin "B12") (pinfunction "EXBG7_B12") (pintype "passive"))
    )
    (net (code "146") (name "unconnected-(CN1-EXBG8-PadA14)") (class "Default")
      (node (ref "CN1") (pin "A14") (pinfunction "EXBG8_A14") (pintype "passive"))
    )
    (net (code "147") (name "unconnected-(CN1-EXBG9-PadB14)") (class "Default")
      (node (ref "CN1") (pin "B14") (pinfunction "EXBG9_B14") (pintype "passive"))
    )
    (net (code "148") (name "unconnected-(CN1-EXBG10-PadA15)") (class "Default")
      (node (ref "CN1") (pin "A15") (pinfunction "EXBG10_A15") (pintype "passive"))
    )
    (net (code "149") (name "unconnected-(CN1-EXBG11-PadB15)") (class "Default")
      (node (ref "CN1") (pin "B15") (pinfunction "EXBG11_B15") (pintype "passive"))
    )
    (net (code "150") (name "unconnected-(CN1-EXBG12-PadA16)") (class "Default")
      (node (ref "CN1") (pin "A16") (pinfunction "EXBG12_A16") (pintype "passive"))
    )
    (net (code "151") (name "unconnected-(CN1-EXBG13-PadB16)") (class "Default")
      (node (ref "CN1") (pin "B16") (pinfunction "EXBG13_B16") (pintype "passive"))
    )
    (net (code "152") (name "unconnected-(CN1-EXBG14-PadA17)") (class "Default")
      (node (ref "CN1") (pin "A17") (pinfunction "EXBG14_A17") (pintype "passive"))
    )
    (net (code "153") (name "unconnected-(CN1-EXBG15-PadB17)") (class "Default")
      (node (ref "CN1") (pin "B17") (pinfunction "EXBG15_B17") (pintype "passive"))
    )
    (net (code "154") (name "unconnected-(CN1-EXBG16-PadA19)") (class "Default")
      (node (ref "CN1") (pin "A19") (pinfunction "EXBG16_A19") (pintype "passive"))
    )
    (net (code "155") (name "unconnected-(CN1-EXBG17-PadB19)") (class "Default")
      (node (ref "CN1") (pin "B19") (pinfunction "EXBG17_B19") (pintype "passive"))
    )
    (net (code "156") (name "unconnected-(CN1-EXBG18-PadA20)") (class "Default")
      (node (ref "CN1") (pin "A20") (pinfunction "EXBG18_A20") (pintype "passive"))
    )
    (net (code "157") (name "unconnected-(CN1-EXBG19-PadB20)") (class "Default")
      (node (ref "CN1") (pin "B20") (pinfunction "EXBG19_B20") (pintype "passive"))
    )
    (net (code "158") (name "unconnected-(CN1-EXBG20-PadA21)") (class "Default")
      (node (ref "CN1") (pin "A21") (pinfunction "EXBG20_A21") (pintype "passive"))
    )
    (net (code "159") (name "unconnected-(CN1-EXBG21-PadB21)") (class "Default")
      (node (ref "CN1") (pin "B21") (pinfunction "EXBG21_B21") (pintype "passive"))
    )
    (net (code "160") (name "unconnected-(CN1-EXBG22-PadA22)") (class "Default")
      (node (ref "CN1") (pin "A22") (pinfunction "EXBG22_A22") (pintype "passive"))
    )
    (net (code "161") (name "unconnected-(CN1-EXBG23-PadB22)") (class "Default")
      (node (ref "CN1") (pin "B22") (pinfunction "EXBG23_B22") (pintype "passive"))
    )
    (net (code "162") (name "unconnected-(CN1-~{COPRES}-PadA66)") (class "Default")
      (node (ref "CN1") (pin "A66") (pinfunction "~{COPRES}_A66") (pintype "passive"))
    )
    (net (code "163") (name "unconnected-(CN1-~{EXD}N-PadA24)") (class "Default")
      (node (ref "CN1") (pin "A24") (pinfunction "~{EXD}N_A24") (pintype "passive"))
    )
    (net (code "164") (name "unconnected-(CN1-~{EXLAT}-PadA25)") (class "Default")
      (node (ref "CN1") (pin "A25") (pinfunction "~{EXLAT}_A25") (pintype "passive"))
    )
    (net (code "165") (name "unconnected-(CN1-~{EXSL}-PadB25)") (class "Default")
      (node (ref "CN1") (pin "B25") (pinfunction "~{EXSL}_B25") (pintype "passive"))
    )
    (net (code "166") (name "unconnected-(CN1-~{EXSYNC}-PadB28)") (class "Default")
      (node (ref "CN1") (pin "B28") (pinfunction "~{EXSYNC}_B28") (pintype "passive"))
    )
    (net (code "167") (name "unconnected-(CN1-~{HSYNC}-PadA26)") (class "Default")
      (node (ref "CN1") (pin "A26") (pinfunction "~{HSYNC}_A26") (pintype "passive"))
    )
    (net (code "168") (name "unconnected-(CN1-~{MPEGON}-PadB24)") (class "Default")
      (node (ref "CN1") (pin "B24") (pinfunction "~{MPEGON}_B24") (pintype "passive"))
    )
    (net (code "169") (name "unconnected-(CN1-~{VSYNC}-PadB26)") (class "Default")
      (node (ref "CN1") (pin "B26") (pinfunction "~{VSYNC}_B26") (pintype "passive"))
    )
    (net (code "170") (name "unconnected-(U1-2A5-Pad30)") (class "Default")
      (node (ref "U1") (pin "30") (pinfunction "2A5_30") (pintype "passive"))
    )
    (net (code "171") (name "unconnected-(U1-2B5-Pad19)") (class "Default")
      (node (ref "U1") (pin "19") (pinfunction "2B5_19") (pintype "passive"))
    )
    (net (code "172") (name "unconnected-(U4-2A5-Pad30)") (class "Default")
      (node (ref "U4") (pin "30") (pinfunction "2A5_30") (pintype "passive"))
    )
    (net (code "173") (name "unconnected-(U4-2A6-Pad29)") (class "Default")
      (node (ref "U4") (pin "29") (pinfunction "2A6_29") (pintype "passive"))
    )
    (net (code "174") (name "unconnected-(U4-2B5-Pad19)") (class "Default")
      (node (ref "U4") (pin "19") (pinfunction "2B5_19") (pintype "passive"))
    )
    (net (code "175") (name "unconnected-(U4-2B6-Pad20)") (class "Default")
      (node (ref "U4") (pin "20") (pinfunction "2B6_20") (pintype "passive"))
    )
    (net (code "176") (name "unconnected-(U5D-IO,_DIFFIO_B13p-PadK9)") (class "Default")
      (node (ref "U5") (pin "K9") (pinfunction "IO,_DIFFIO_B13p_K9") (pintype "bidirectional"))
    )
    (net (code "177") (name "unconnected-(U5D-IO,_DIFFIO_B18p-PadK10)") (class "Default")
      (node (ref "U5") (pin "K10") (pinfunction "IO,_DIFFIO_B18p_K10") (pintype "bidirectional"))
    )
    (net (code "178") (name "unconnected-(U5D-IO,_DIFFIO_B21n-PadL11)") (class "Default")
      (node (ref "U5") (pin "L11") (pinfunction "IO,_DIFFIO_B21n_L11") (pintype "bidirectional"))
    )
    (net (code "179") (name "unconnected-(U5D-IO,_DIFFIO_B22p-PadM11)") (class "Default")
      (node (ref "U5") (pin "M11") (pinfunction "IO,_DIFFIO_B22p_M11") (pintype "bidirectional"))
    )
    (net (code "180") (name "unconnected-(U5E-IO-PadK11)") (class "Default")
      (node (ref "U5") (pin "K11") (pinfunction "IO_K11") (pintype "bidirectional"))
    )
  )
)
